# schematic.net
KiCad netlist of a schematic drawn in EasyEDA
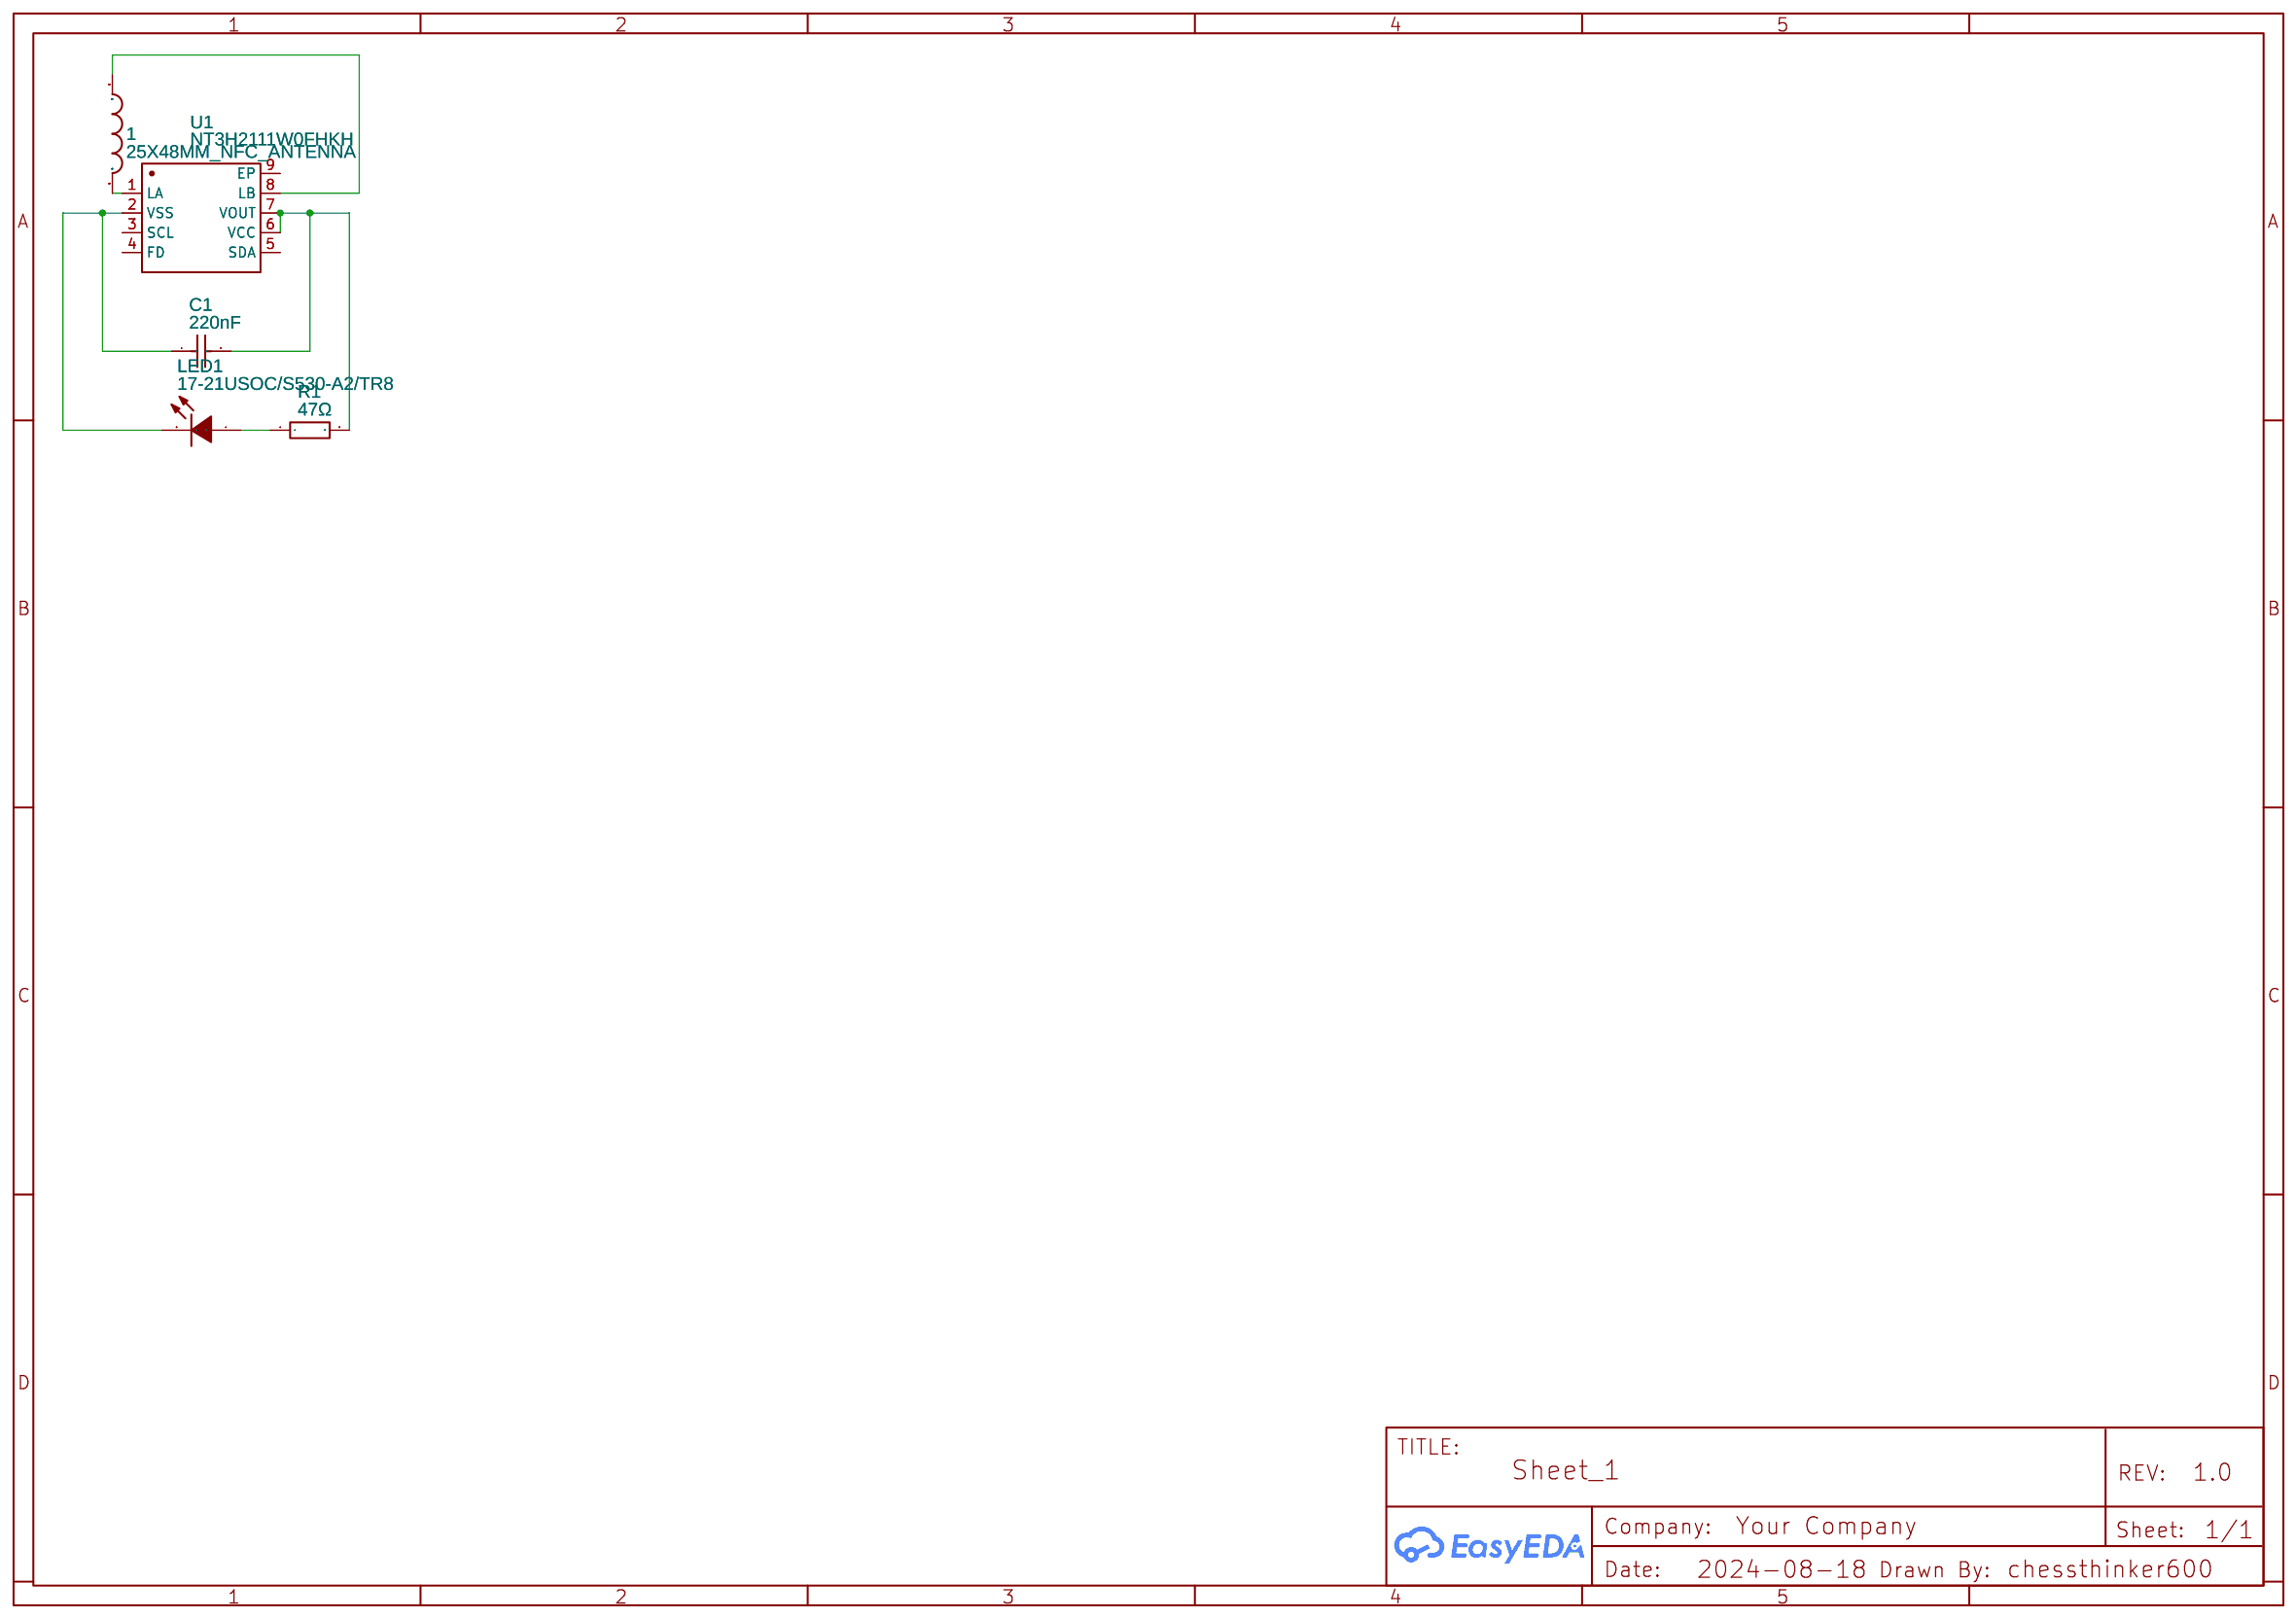
[diagram p0: schematic sheet]

(export (version "E")
  (design (tool "Eeschema 10.0.6"))
  (components
    (comp (ref "1") (value "25X48MM_NFC_ANTENNA") (libsource (lib "") (part "25X48MM_NFC_ANTENNA")))
    (comp (ref "C1")
      (value "220nF")
      (fields
        (field (name "Manufacturer Part") "CL10B224KA8NNNC")
        (field (name "Manufacturer") "SAMSUNG(三星)")
      )
      (libsource (lib "") (part "CL10B224KA8NNNC"))
    )
    (comp (ref "LED1")
      (value "17-21USOC/S530-A2/TR8")
      (fields (field (name "Manufacturer") "EVERLIGHT(亿光)"))
      (libsource (lib "") (part "17-21USOC/S530-A2/TR8"))
    )
    (comp (ref "R1")
      (value "47Ω")
      (fields
        (field (name "Manufacturer Part") "0603WAF470JT5E")
        (field (name "Manufacturer") "UNI-ROYAL(厚声)")
      )
      (libsource (lib "") (part "0603WAF470JT5E"))
    )
    (comp (ref "U1")
      (value "NT3H2111W0FHKH")
      (fields (field (name "Manufacturer") "NXP(恩智浦)"))
      (libsource (lib "") (part "NT3H2111W0FHKH"))
    )
  )
  (nets
    (net (code "1") (name "Net-(LED1-A)") (class "Default")
      (node (ref "LED1") (pin "1") (pinfunction "A_1") (pintype "unspecified"))
      (node (ref "R1") (pin "1") (pinfunction "1_1") (pintype "input"))
    )
    (net (code "2") (name "Net-(LED1-K)") (class "Default")
      (node (ref "C1") (pin "1") (pinfunction "1_1") (pintype "input"))
      (node (ref "LED1") (pin "2") (pinfunction "K_2") (pintype "unspecified"))
      (node (ref "U1") (pin "2") (pinfunction "VSS_2") (pintype "unspecified"))
    )
    (net (code "3") (name "Net-(U1-LA)") (class "Default")
      (node (ref "1") (pin "P$2") (pinfunction "P$2_P$2") (pintype "bidirectional"))
      (node (ref "U1") (pin "1") (pinfunction "LA_1") (pintype "unspecified"))
    )
    (net (code "4") (name "Net-(U1-LB)") (class "Default")
      (node (ref "1") (pin "P$1") (pinfunction "P$1_P$1") (pintype "bidirectional"))
      (node (ref "U1") (pin "8") (pinfunction "LB_8") (pintype "unspecified"))
    )
    (net (code "5") (name "Net-(U1-VCC)") (class "Default")
      (node (ref "C1") (pin "2") (pinfunction "2_2") (pintype "input"))
      (node (ref "R1") (pin "2") (pinfunction "2_2") (pintype "input"))
      (node (ref "U1") (pin "6") (pinfunction "VCC_6") (pintype "unspecified"))
      (node (ref "U1") (pin "7") (pinfunction "VOUT_7") (pintype "unspecified"))
    )
    (net (code "6") (name "unconnected-(U1-EP-Pad9)") (class "Default")
      (node (ref "U1") (pin "9") (pinfunction "EP_9") (pintype "unspecified"))
    )
    (net (code "7") (name "unconnected-(U1-FD-Pad4)") (class "Default")
      (node (ref "U1") (pin "4") (pinfunction "FD_4") (pintype "unspecified"))
    )
    (net (code "8") (name "unconnected-(U1-SCL-Pad3)") (class "Default")
      (node (ref "U1") (pin "3") (pinfunction "SCL_3") (pintype "unspecified"))
    )
    (net (code "9") (name "unconnected-(U1-SDA-Pad5)") (class "Default")
      (node (ref "U1") (pin "5") (pinfunction "SDA_5") (pintype "unspecified"))
    )
  )
)
